# rs232-npn-pnp-negative-mirrored-alt.net
KiCad netlist of a schematic drawn in EAGLE
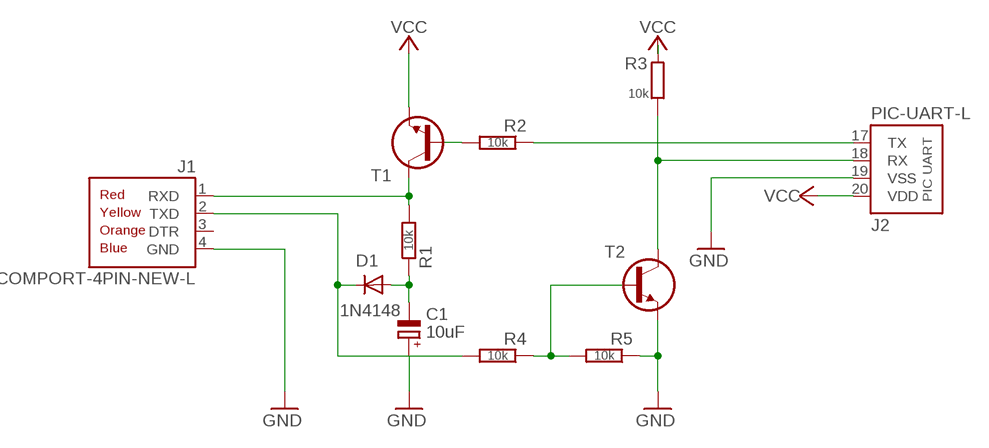
[diagram p0: schematic, sheet 1]

(export (version "E")
  (design (tool "Eeschema 10.0.6"))
  (components
    (comp (ref "C1")
      (value "10uF")
      (footprint "eagle-import:E2,5-5")
      (libsource (lib "eagle-import") (part "CPOLE2.5-5"))
    )
    (comp (ref "D1")
      (value "1N4148")
      (footprint "eagle-import:DO34-5V")
      (libsource (lib "eagle-import") (part "1N414834-5V"))
    )
    (comp (ref "J1")
      (value "COMPORT-4PIN-NEW-L")
      (footprint "eagle-import:RS232-4PIN-NEW-L")
      (libsource (lib "eagle-import") (part "COMPORT-4PIN-NEW-L"))
    )
    (comp (ref "J2")
      (value "PIC-UART-L")
      (footprint "eagle-import:PIC-UART-L")
      (libsource (lib "eagle-import") (part "PIC-UART-L"))
    )
    (comp (ref "R1")
      (value "10k")
      (footprint "eagle-import:0202_7")
      (libsource (lib "eagle-import") (part "R0202/7"))
    )
    (comp (ref "R2")
      (value "10k")
      (footprint "eagle-import:0202_7")
      (libsource (lib "eagle-import") (part "R0202/7"))
    )
    (comp (ref "R3")
      (value "10k")
      (footprint "eagle-import:0202_7-V")
      (libsource (lib "eagle-import") (part "R0202/7-V"))
    )
    (comp (ref "R4")
      (value "10k")
      (footprint "eagle-import:0202_7")
      (libsource (lib "eagle-import") (part "R0202/7"))
    )
    (comp (ref "R5")
      (value "10k")
      (footprint "eagle-import:0202_7-V")
      (libsource (lib "eagle-import") (part "R0202/7-V"))
    )
    (comp (ref "T1")
      (value "BC547")
      (footprint "eagle-import:TO92-CBE")
      (libsource (lib "eagle-import") (part "BC547CBE"))
    )
    (comp (ref "T2")
      (value "BC547")
      (footprint "eagle-import:TO92-CBE")
      (libsource (lib "eagle-import") (part "BC547CBE"))
    )
  )
  (nets
    (net (code "1") (name "GND") (class "Default")
      (node (ref "C1") (pin "+") (pinfunction "+_+") (pintype "passive"))
      (node (ref "J1") (pin "4") (pinfunction "GND_4") (pintype "passive"))
      (node (ref "J2") (pin "19") (pinfunction "VSS_19") (pintype "passive"))
      (node (ref "R5") (pin "1") (pinfunction "1_1") (pintype "passive"))
      (node (ref "T2") (pin "E") (pinfunction "E_E") (pintype "passive"))
    )
    (net (code "2") (name "Net-(C1-Pad-)") (class "Default")
      (node (ref "C1") (pin "-") (pinfunction "-_-") (pintype "passive"))
      (node (ref "D1") (pin "A") (pinfunction "A_A") (pintype "passive"))
      (node (ref "R1") (pin "1") (pinfunction "1_1") (pintype "passive"))
    )
    (net (code "3") (name "Net-(J1-RXD)") (class "Default")
      (node (ref "J1") (pin "1") (pinfunction "RXD_1") (pintype "passive"))
      (node (ref "R1") (pin "2") (pinfunction "2_2") (pintype "passive"))
      (node (ref "T1") (pin "C") (pinfunction "C_C") (pintype "passive"))
    )
    (net (code "4") (name "Net-(J1-TXD)") (class "Default")
      (node (ref "D1") (pin "C") (pinfunction "C_C") (pintype "passive"))
      (node (ref "J1") (pin "2") (pinfunction "TXD_2") (pintype "passive"))
      (node (ref "R4") (pin "2") (pinfunction "2_2") (pintype "passive"))
    )
    (net (code "5") (name "Net-(J2-RX)") (class "Default")
      (node (ref "J2") (pin "18") (pinfunction "RX_18") (pintype "passive"))
      (node (ref "R3") (pin "1") (pinfunction "1_1") (pintype "passive"))
      (node (ref "T2") (pin "C") (pinfunction "C_C") (pintype "passive"))
    )
    (net (code "6") (name "Net-(J2-TX)") (class "Default")
      (node (ref "J2") (pin "17") (pinfunction "TX_17") (pintype "passive"))
      (node (ref "R2") (pin "1") (pinfunction "1_1") (pintype "passive"))
    )
    (net (code "7") (name "Net-(R2-Pad2)") (class "Default")
      (node (ref "R2") (pin "2") (pinfunction "2_2") (pintype "passive"))
      (node (ref "T1") (pin "B") (pinfunction "B_B") (pintype "passive"))
    )
    (net (code "8") (name "Net-(R4-Pad1)") (class "Default")
      (node (ref "R4") (pin "1") (pinfunction "1_1") (pintype "passive"))
      (node (ref "R5") (pin "2") (pinfunction "2_2") (pintype "passive"))
      (node (ref "T2") (pin "B") (pinfunction "B_B") (pintype "passive"))
    )
    (net (code "9") (name "VCC") (class "Default")
      (node (ref "J2") (pin "20") (pinfunction "VDD_20") (pintype "passive"))
      (node (ref "R3") (pin "2") (pinfunction "2_2") (pintype "passive"))
      (node (ref "T1") (pin "E") (pinfunction "E_E") (pintype "passive"))
    )
    (net (code "10") (name "unconnected-(J1-DTR-Pad3)") (class "Default")
      (node (ref "J1") (pin "3") (pinfunction "DTR_3") (pintype "passive"))
    )
  )
)
